# nRF52832_MCU.net
KiCad netlist of a schematic drawn in EAGLE
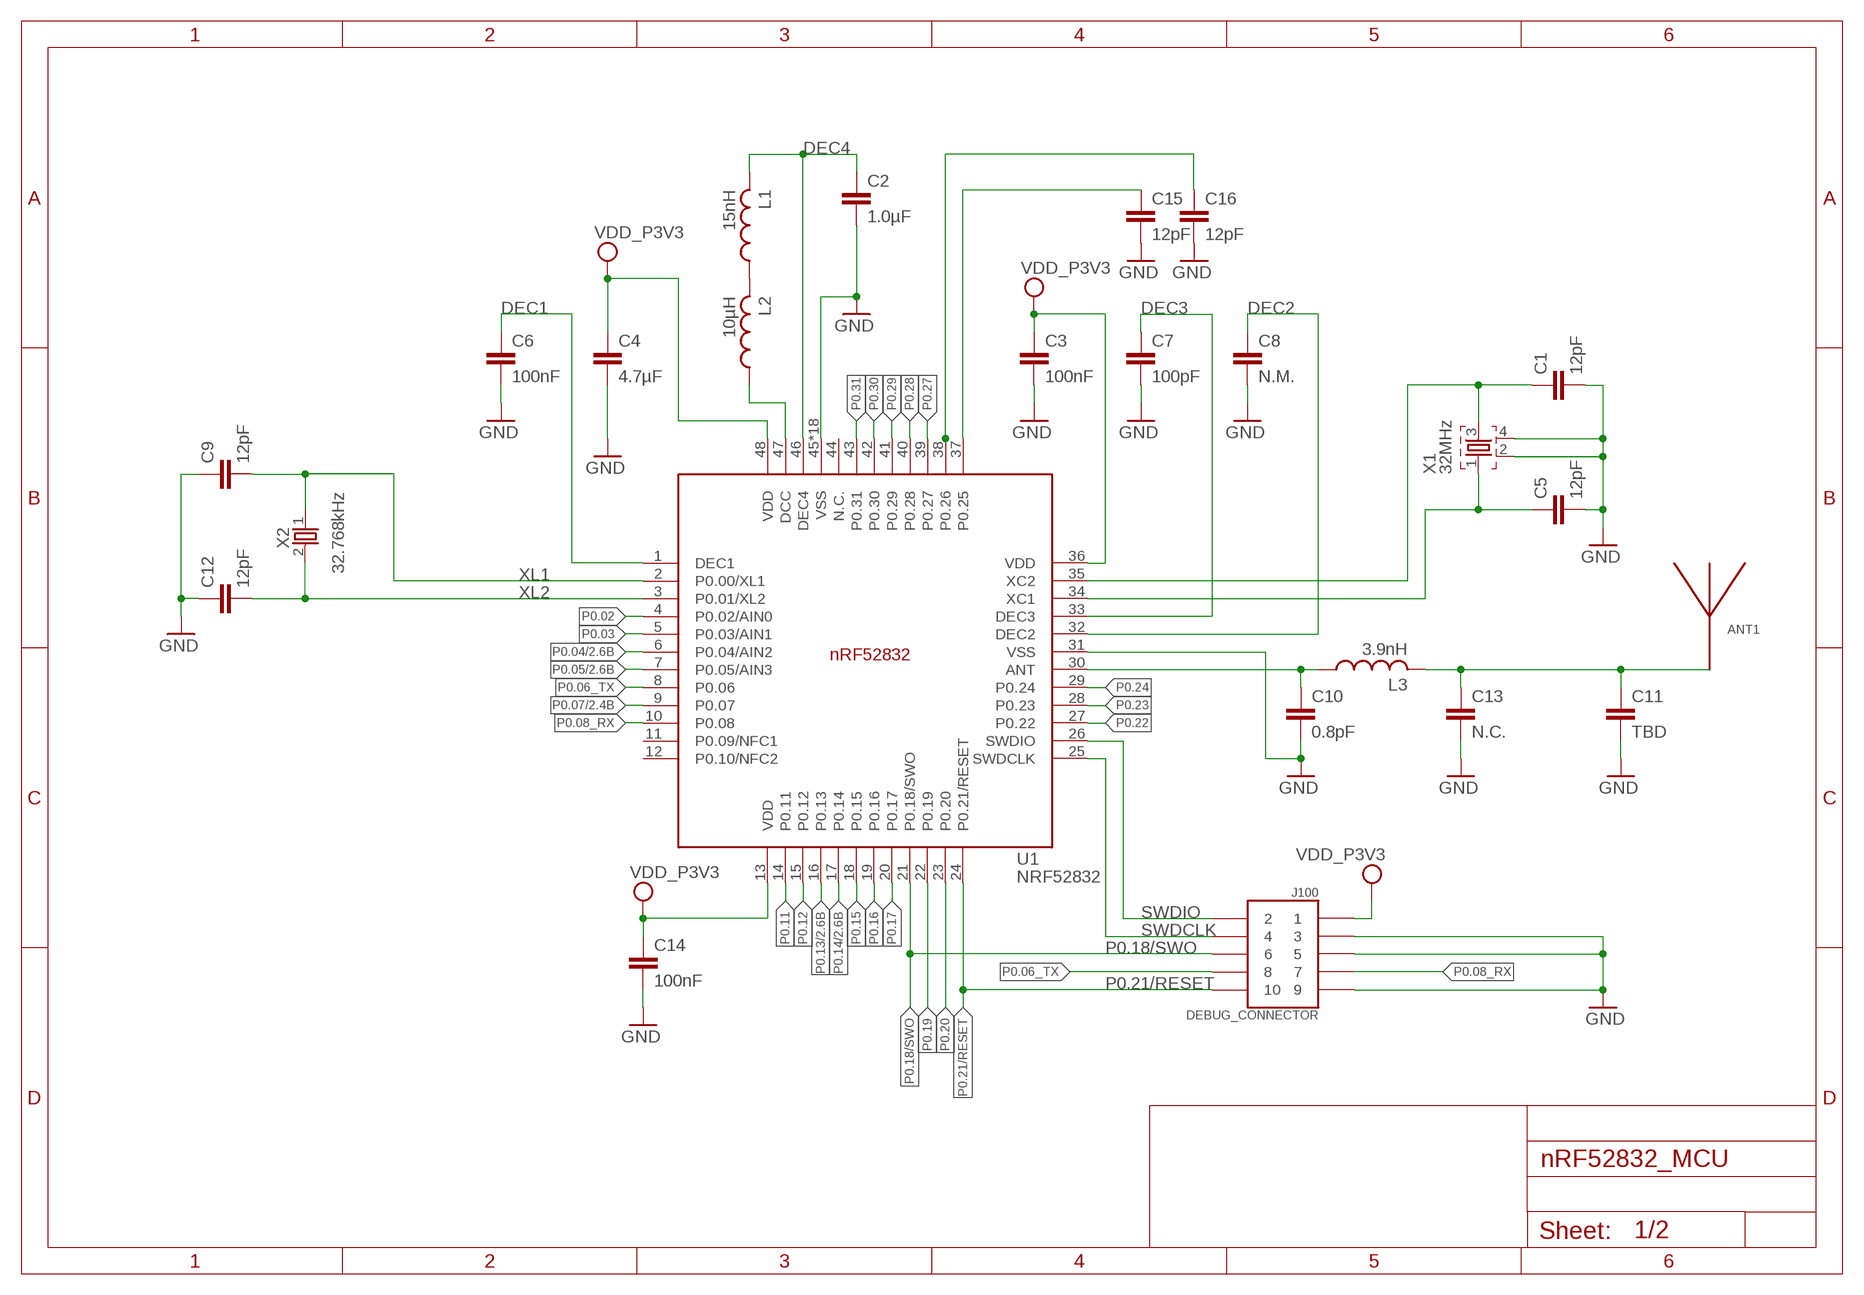
[diagram p0: schematic, sheet 1]
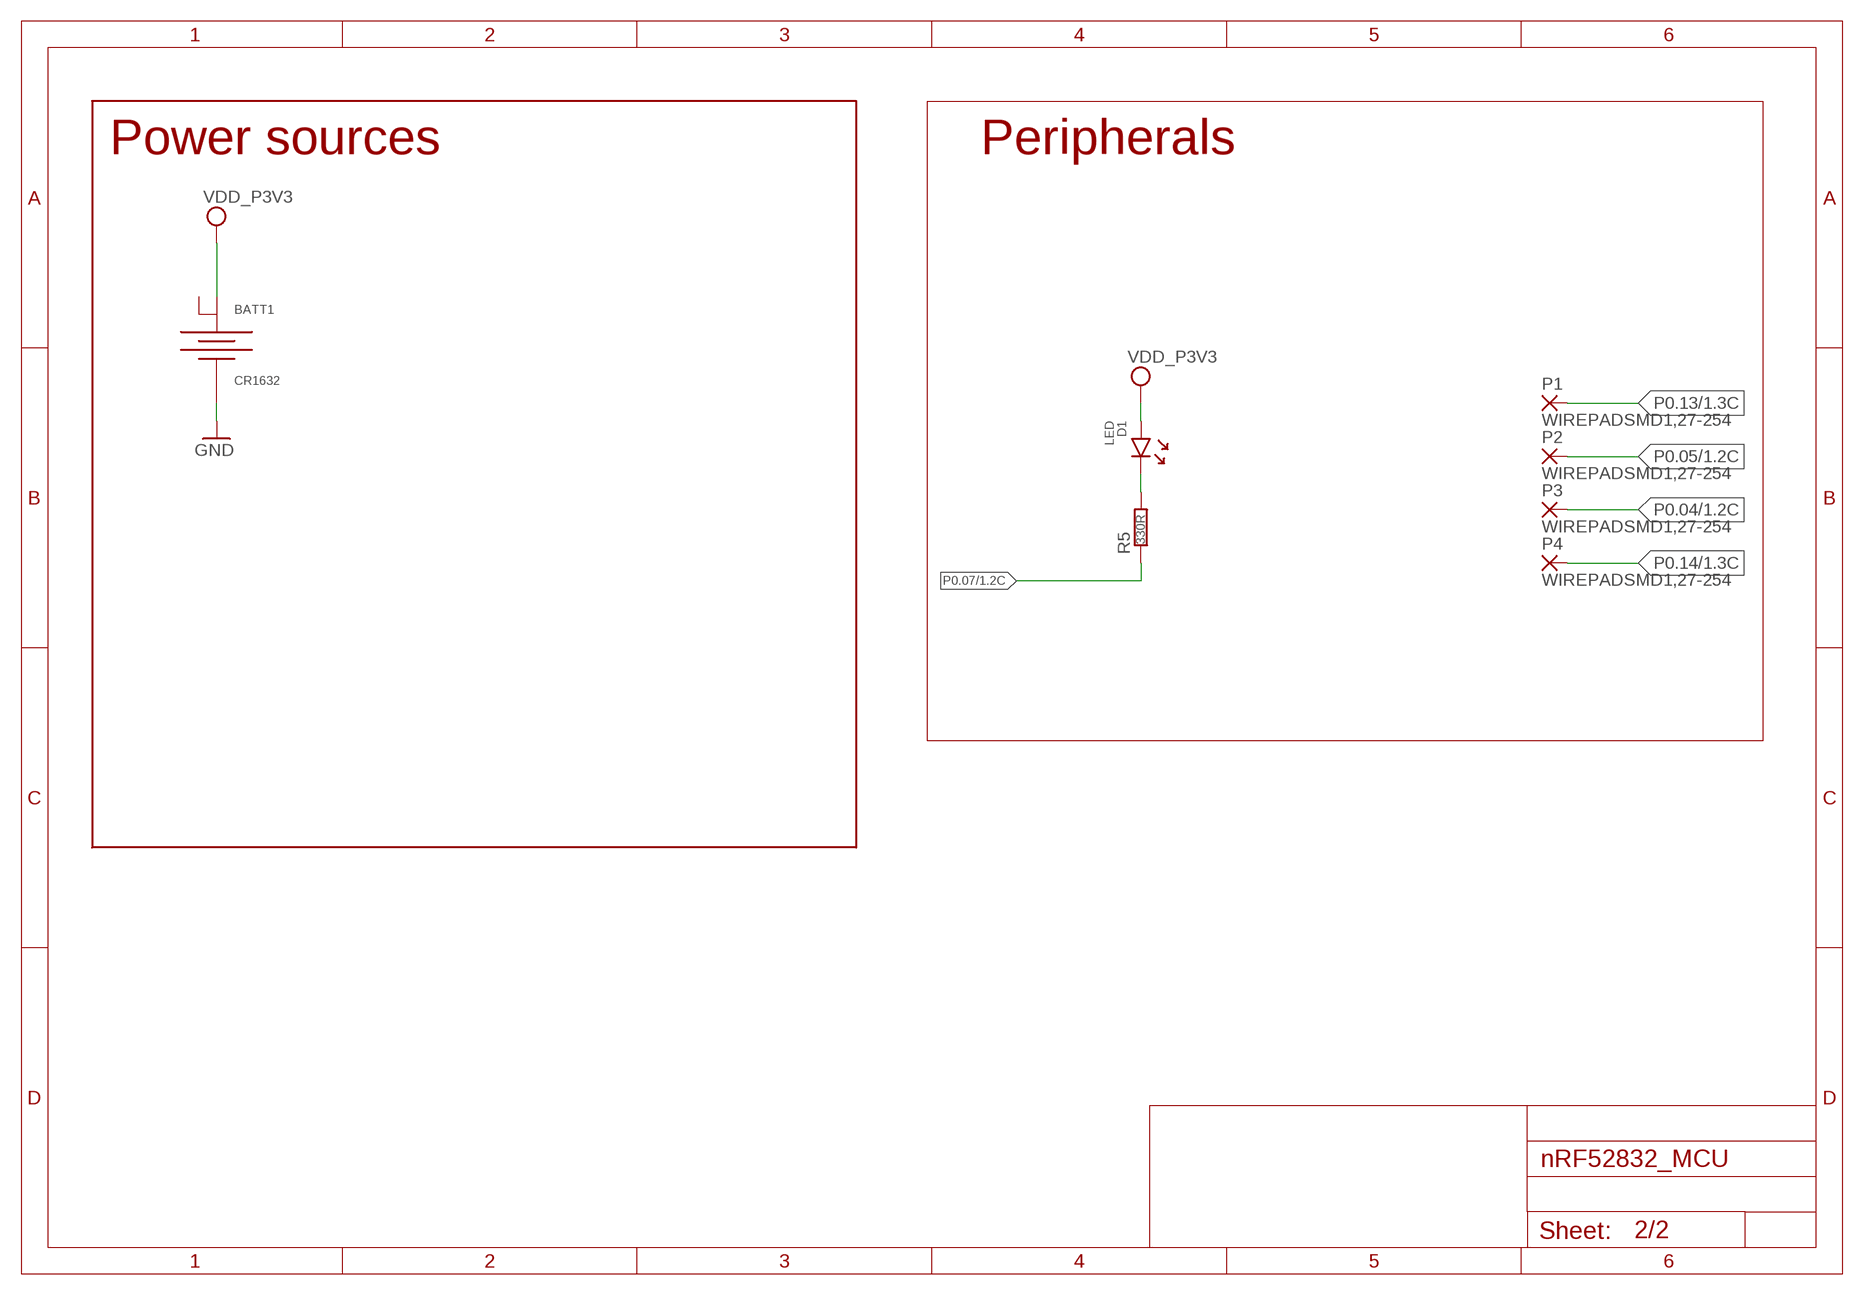
[diagram p1: schematic, sheet 2]

(export (version "E")
  (design (tool "Eeschema 10.0.6"))
  (components
    (comp (ref "BATT1")
      (value "CR1632")
      (footprint "eagle-import:CR1632_HOLDER_TH")
      (libsource (lib "eagle-import") (part "CR1632"))
    )
    (comp (ref "D1")
      (value "LED")
      (footprint "eagle-import:DIOC0603_N")
      (libsource (lib "eagle-import") (part "LED"))
    )
    (comp (ref "P1")
      (value "WIREPADSMD1,27-254")
      (footprint "eagle-import:SMD1,27-2,54")
      (libsource (lib "eagle-import") (part "WIREPADSMD1,27-254"))
    )
    (comp (ref "P2")
      (value "WIREPADSMD1,27-254")
      (footprint "eagle-import:SMD1,27-2,54")
      (libsource (lib "eagle-import") (part "WIREPADSMD1,27-254"))
    )
    (comp (ref "P3")
      (value "WIREPADSMD1,27-254")
      (footprint "eagle-import:SMD1,27-2,54")
      (libsource (lib "eagle-import") (part "WIREPADSMD1,27-254"))
    )
    (comp (ref "P4")
      (value "WIREPADSMD1,27-254")
      (footprint "eagle-import:SMD1,27-2,54")
      (libsource (lib "eagle-import") (part "WIREPADSMD1,27-254"))
    )
    (comp (ref "R5")
      (value "330R")
      (footprint "eagle-import:RESC0402_N")
      (libsource (lib "eagle-import") (part "RESISTOR_0402_N"))
    )
    (comp (ref "ANT1")
      (value "ANTENNA_QUARTER-WAVE_MONOPOLE_MEANDERED_LEFT")
      (footprint "eagle-import:QWMP_MEANDERED_LEFT_+6")
      (libsource (lib "eagle-import") (part "ANTENNA_QUARTER-WAVE_MONOPOLE_MEANDERED_LEFT"))
    )
    (comp (ref "C1")
      (value "12pF")
      (footprint "eagle-import:RESC0402_N")
      (libsource (lib "eagle-import") (part "CAPACITOR_0402_N"))
    )
    (comp (ref "C2")
      (value "1.0µF")
      (footprint "eagle-import:RESC0603_N")
      (libsource (lib "eagle-import") (part "CAPACITOR_0603_N"))
    )
    (comp (ref "C3")
      (value "100nF")
      (footprint "eagle-import:RESC0402_N")
      (libsource (lib "eagle-import") (part "CAPACITOR_0402_N"))
    )
    (comp (ref "C4")
      (value "4.7µF")
      (footprint "eagle-import:RESC0603_N")
      (libsource (lib "eagle-import") (part "CAPACITOR_0603_N"))
    )
    (comp (ref "C5")
      (value "12pF")
      (footprint "eagle-import:RESC0402_N")
      (libsource (lib "eagle-import") (part "CAPACITOR_0402_N"))
    )
    (comp (ref "C6")
      (value "100nF")
      (footprint "eagle-import:RESC0402_N")
      (libsource (lib "eagle-import") (part "CAPACITOR_0402_N"))
    )
    (comp (ref "C7")
      (value "100pF")
      (footprint "eagle-import:RESC0402_N")
      (libsource (lib "eagle-import") (part "CAPACITOR_0402_N"))
    )
    (comp (ref "C8")
      (value "N.M.")
      (footprint "eagle-import:RESC0402_N")
      (libsource (lib "eagle-import") (part "CAPACITOR_0402_N"))
    )
    (comp (ref "C9")
      (value "12pF")
      (footprint "eagle-import:RESC0402_N")
      (libsource (lib "eagle-import") (part "CAPACITOR_0402_N"))
    )
    (comp (ref "C10")
      (value "0.8pF")
      (footprint "eagle-import:RESC0402_N")
      (libsource (lib "eagle-import") (part "CAPACITOR_0402_N"))
    )
    (comp (ref "C11")
      (value "TBD")
      (footprint "eagle-import:RESC0402_N")
      (libsource (lib "eagle-import") (part "CAPACITOR_0402_N"))
    )
    (comp (ref "C12")
      (value "12pF")
      (footprint "eagle-import:RESC0402_N")
      (libsource (lib "eagle-import") (part "CAPACITOR_0402_N"))
    )
    (comp (ref "C13")
      (value "N.C.")
      (footprint "eagle-import:RESC0402_N")
      (libsource (lib "eagle-import") (part "CAPACITOR_0402_N"))
    )
    (comp (ref "C14")
      (value "100nF")
      (footprint "eagle-import:RESC0402_N")
      (libsource (lib "eagle-import") (part "CAPACITOR_0402_N"))
    )
    (comp (ref "C15")
      (value "12pF")
      (footprint "eagle-import:RESC0402_N")
      (libsource (lib "eagle-import") (part "CAPACITOR_0402_N"))
    )
    (comp (ref "C16")
      (value "12pF")
      (footprint "eagle-import:RESC0402_N")
      (libsource (lib "eagle-import") (part "CAPACITOR_0402_N"))
    )
    (comp (ref "J100")
      (value "DEBUG_CONNECTOR")
      (footprint "eagle-import:HDRV127P5X2-10_N")
      (libsource (lib "eagle-import") (part "DEBUG_CONNECTOR"))
    )
    (comp (ref "L1")
      (value "15nH")
      (footprint "eagle-import:RESC0402_N")
      (libsource (lib "eagle-import") (part "INDUCTOR_0402_N"))
    )
    (comp (ref "L2")
      (value "10µH")
      (footprint "eagle-import:RESC0603_N")
      (libsource (lib "eagle-import") (part "INDUCTOR_0603_N"))
    )
    (comp (ref "L3")
      (value "3.9nH")
      (footprint "eagle-import:RESC0402_N")
      (libsource (lib "eagle-import") (part "INDUCTOR_0402_N"))
    )
    (comp (ref "U1")
      (value "NRF52832")
      (footprint "eagle-import:QFN40P600X600X90-48_N")
      (libsource (lib "eagle-import") (part "NRF52832"))
    )
    (comp (ref "X1")
      (value "32MHz")
      (footprint "eagle-import:BT-XTAL_2016_N")
      (libsource (lib "eagle-import") (part "XTAL_32MHZ"))
    )
    (comp (ref "X2")
      (value "32.768kHz")
      (footprint "eagle-import:XTAL_3215_N")
      (libsource (lib "eagle-import") (part "XTAL_32KHZ"))
    )
  )
  (nets
    (net (code "1") (name "DEC1") (class "Default")
      (node (ref "C6") (pin "1") (pinfunction "1_1") (pintype "passive"))
      (node (ref "U1") (pin "1") (pinfunction "DEC1_1") (pintype "power_in"))
    )
    (net (code "2") (name "DEC2") (class "Default")
      (node (ref "C8") (pin "1") (pinfunction "1_1") (pintype "passive"))
      (node (ref "U1") (pin "32") (pinfunction "DEC2_32") (pintype "bidirectional"))
    )
    (net (code "3") (name "DEC3") (class "Default")
      (node (ref "C7") (pin "1") (pinfunction "1_1") (pintype "passive"))
      (node (ref "U1") (pin "33") (pinfunction "DEC3_33") (pintype "bidirectional"))
    )
    (net (code "4") (name "DEC4") (class "Default")
      (node (ref "C2") (pin "1") (pinfunction "1_1") (pintype "passive"))
      (node (ref "L1") (pin "2") (pinfunction "2_2") (pintype "passive"))
      (node (ref "U1") (pin "46") (pinfunction "DEC4_46") (pintype "power_in"))
    )
    (net (code "5") (name "GND") (class "Default")
      (node (ref "BATT1") (pin "1") (pinfunction "-_1") (pintype "bidirectional"))
      (node (ref "C1") (pin "2") (pinfunction "2_2") (pintype "passive"))
      (node (ref "C10") (pin "2") (pinfunction "2_2") (pintype "passive"))
      (node (ref "C11") (pin "2") (pinfunction "2_2") (pintype "passive"))
      (node (ref "C12") (pin "1") (pinfunction "1_1") (pintype "passive"))
      (node (ref "C13") (pin "2") (pinfunction "2_2") (pintype "passive"))
      (node (ref "C14") (pin "2") (pinfunction "2_2") (pintype "passive"))
      (node (ref "C15") (pin "2") (pinfunction "2_2") (pintype "passive"))
      (node (ref "C16") (pin "2") (pinfunction "2_2") (pintype "passive"))
      (node (ref "C2") (pin "2") (pinfunction "2_2") (pintype "passive"))
      (node (ref "C3") (pin "2") (pinfunction "2_2") (pintype "passive"))
      (node (ref "C4") (pin "2") (pinfunction "2_2") (pintype "passive"))
      (node (ref "C5") (pin "2") (pinfunction "2_2") (pintype "passive"))
      (node (ref "C6") (pin "2") (pinfunction "2_2") (pintype "passive"))
      (node (ref "C7") (pin "2") (pinfunction "2_2") (pintype "passive"))
      (node (ref "C8") (pin "2") (pinfunction "2_2") (pintype "passive"))
      (node (ref "C9") (pin "1") (pinfunction "1_1") (pintype "passive"))
      (node (ref "J100") (pin "3") (pinfunction "3_3") (pintype "bidirectional"))
      (node (ref "J100") (pin "5") (pinfunction "5_5") (pintype "bidirectional"))
      (node (ref "J100") (pin "9") (pinfunction "9_9") (pintype "bidirectional"))
      (node (ref "U1") (pin "31") (pinfunction "VSS_31") (pintype "bidirectional"))
      (node (ref "U1") (pin "45") (pinfunction "VSS_45") (pintype "power_in"))
      (node (ref "U1") (pin "PAD") (pinfunction "VSS_PAD") (pintype "power_in"))
      (node (ref "U1") (pin "PAD@VIA01") (pinfunction "VSS_PAD@VIA01") (pintype "power_in"))
      (node (ref "U1") (pin "PAD@VIA02") (pinfunction "VSS_PAD@VIA02") (pintype "power_in"))
      (node (ref "U1") (pin "PAD@VIA03") (pinfunction "VSS_PAD@VIA03") (pintype "power_in"))
      (node (ref "U1") (pin "PAD@VIA04") (pinfunction "VSS_PAD@VIA04") (pintype "power_in"))
      (node (ref "U1") (pin "PAD@VIA05") (pinfunction "VSS_PAD@VIA05") (pintype "power_in"))
      (node (ref "U1") (pin "PAD@VIA06") (pinfunction "VSS_PAD@VIA06") (pintype "power_in"))
      (node (ref "U1") (pin "PAD@VIA07") (pinfunction "VSS_PAD@VIA07") (pintype "power_in"))
      (node (ref "U1") (pin "PAD@VIA08") (pinfunction "VSS_PAD@VIA08") (pintype "power_in"))
      (node (ref "U1") (pin "PAD@VIA09") (pinfunction "VSS_PAD@VIA09") (pintype "power_in"))
      (node (ref "U1") (pin "PAD@VIA10") (pinfunction "VSS_PAD@VIA10") (pintype "power_in"))
      (node (ref "U1") (pin "PAD@VIA11") (pinfunction "VSS_PAD@VIA11") (pintype "power_in"))
      (node (ref "U1") (pin "PAD@VIA12") (pinfunction "VSS_PAD@VIA12") (pintype "power_in"))
      (node (ref "U1") (pin "PAD@VIA13") (pinfunction "VSS_PAD@VIA13") (pintype "power_in"))
      (node (ref "U1") (pin "PAD@VIA14") (pinfunction "VSS_PAD@VIA14") (pintype "power_in"))
      (node (ref "U1") (pin "PAD@VIA15") (pinfunction "VSS_PAD@VIA15") (pintype "power_in"))
      (node (ref "U1") (pin "PAD@VIA16") (pinfunction "VSS_PAD@VIA16") (pintype "power_in"))
      (node (ref "X1") (pin "2") (pinfunction "2_2") (pintype "passive"))
      (node (ref "X1") (pin "4") (pinfunction "4_4") (pintype "passive"))
    )
    (net (code "6") (name "Net-(ANT1-PadP$1)") (class "Default")
      (node (ref "ANT1") (pin "P$1") (pinfunction "P$1_P$1") (pintype "bidirectional"))
      (node (ref "C11") (pin "1") (pinfunction "1_1") (pintype "passive"))
      (node (ref "C13") (pin "1") (pinfunction "1_1") (pintype "passive"))
      (node (ref "L3") (pin "2") (pinfunction "2_2") (pintype "passive"))
    )
    (net (code "7") (name "Net-(D1-C)") (class "Default")
      (node (ref "D1") (pin "1") (pinfunction "C_1") (pintype "bidirectional"))
      (node (ref "R5") (pin "2") (pinfunction "2_2") (pintype "passive"))
    )
    (net (code "8") (name "Net-(L1-Pad1)") (class "Default")
      (node (ref "L1") (pin "1") (pinfunction "1_1") (pintype "passive"))
      (node (ref "L2") (pin "2") (pinfunction "2_2") (pintype "passive"))
    )
    (net (code "9") (name "Net-(U1-ANT)") (class "Default")
      (node (ref "C10") (pin "1") (pinfunction "1_1") (pintype "passive"))
      (node (ref "L3") (pin "1") (pinfunction "1_1") (pintype "passive"))
      (node (ref "U1") (pin "30") (pinfunction "ANT_30") (pintype "bidirectional"))
    )
    (net (code "10") (name "Net-(U1-DCC)") (class "Default")
      (node (ref "L2") (pin "1") (pinfunction "1_1") (pintype "passive"))
      (node (ref "U1") (pin "47") (pinfunction "DCC_47") (pintype "output"))
    )
    (net (code "11") (name "Net-(U1-P0.25)") (class "Default")
      (node (ref "C15") (pin "1") (pinfunction "1_1") (pintype "passive"))
      (node (ref "U1") (pin "37") (pinfunction "P0.25_37") (pintype "bidirectional"))
    )
    (net (code "12") (name "Net-(U1-P0.26)") (class "Default")
      (node (ref "C16") (pin "1") (pinfunction "1_1") (pintype "passive"))
      (node (ref "U1") (pin "38") (pinfunction "P0.26_38") (pintype "bidirectional"))
    )
    (net (code "13") (name "Net-(U1-XC1)") (class "Default")
      (node (ref "C5") (pin "1") (pinfunction "1_1") (pintype "passive"))
      (node (ref "U1") (pin "34") (pinfunction "XC1_34") (pintype "input"))
      (node (ref "X1") (pin "1") (pinfunction "1_1") (pintype "passive"))
    )
    (net (code "14") (name "Net-(U1-XC2)") (class "Default")
      (node (ref "C1") (pin "1") (pinfunction "1_1") (pintype "passive"))
      (node (ref "U1") (pin "35") (pinfunction "XC2_35") (pintype "output"))
      (node (ref "X1") (pin "3") (pinfunction "3_3") (pintype "passive"))
    )
    (net (code "15") (name "P0.02") (class "Default")
      (node (ref "U1") (pin "4") (pinfunction "P0.02/AIN0_4") (pintype "bidirectional"))
    )
    (net (code "16") (name "P0.03") (class "Default")
      (node (ref "U1") (pin "5") (pinfunction "P0.03/AIN1_5") (pintype "bidirectional"))
    )
    (net (code "17") (name "P0.04") (class "Default")
      (node (ref "P3") (pin "1") (pinfunction "P_1") (pintype "passive"))
      (node (ref "U1") (pin "6") (pinfunction "P0.04/AIN2_6") (pintype "bidirectional"))
    )
    (net (code "18") (name "P0.05") (class "Default")
      (node (ref "P2") (pin "1") (pinfunction "P_1") (pintype "passive"))
      (node (ref "U1") (pin "7") (pinfunction "P0.05/AIN3_7") (pintype "bidirectional"))
    )
    (net (code "19") (name "P0.06_TX") (class "Default")
      (node (ref "J100") (pin "8") (pinfunction "8_8") (pintype "bidirectional"))
      (node (ref "U1") (pin "8") (pinfunction "P0.06_8") (pintype "bidirectional"))
    )
    (net (code "20") (name "P0.07") (class "Default")
      (node (ref "R5") (pin "1") (pinfunction "1_1") (pintype "passive"))
      (node (ref "U1") (pin "9") (pinfunction "P0.07_9") (pintype "bidirectional"))
    )
    (net (code "21") (name "P0.08_RX") (class "Default")
      (node (ref "J100") (pin "7") (pinfunction "7_7") (pintype "bidirectional"))
      (node (ref "U1") (pin "10") (pinfunction "P0.08_10") (pintype "bidirectional"))
    )
    (net (code "22") (name "P0.11") (class "Default")
      (node (ref "U1") (pin "14") (pinfunction "P0.11_14") (pintype "bidirectional"))
    )
    (net (code "23") (name "P0.12") (class "Default")
      (node (ref "U1") (pin "15") (pinfunction "P0.12_15") (pintype "bidirectional"))
    )
    (net (code "24") (name "P0.13") (class "Default")
      (node (ref "P1") (pin "1") (pinfunction "P_1") (pintype "passive"))
      (node (ref "U1") (pin "16") (pinfunction "P0.13_16") (pintype "bidirectional"))
    )
    (net (code "25") (name "P0.14") (class "Default")
      (node (ref "P4") (pin "1") (pinfunction "P_1") (pintype "passive"))
      (node (ref "U1") (pin "17") (pinfunction "P0.14_17") (pintype "bidirectional"))
    )
    (net (code "26") (name "P0.15") (class "Default")
      (node (ref "U1") (pin "18") (pinfunction "P0.15_18") (pintype "bidirectional"))
    )
    (net (code "27") (name "P0.16") (class "Default")
      (node (ref "U1") (pin "19") (pinfunction "P0.16_19") (pintype "bidirectional"))
    )
    (net (code "28") (name "P0.17") (class "Default")
      (node (ref "U1") (pin "20") (pinfunction "P0.17_20") (pintype "bidirectional"))
    )
    (net (code "29") (name "P0.18{slash}SWO") (class "Default")
      (node (ref "J100") (pin "6") (pinfunction "6_6") (pintype "bidirectional"))
      (node (ref "U1") (pin "21") (pinfunction "P0.18/SWO_21") (pintype "bidirectional"))
    )
    (net (code "30") (name "P0.19") (class "Default")
      (node (ref "U1") (pin "22") (pinfunction "P0.19_22") (pintype "bidirectional"))
    )
    (net (code "31") (name "P0.20") (class "Default")
      (node (ref "U1") (pin "23") (pinfunction "P0.20_23") (pintype "bidirectional"))
    )
    (net (code "32") (name "P0.21{slash}RESET") (class "Default")
      (node (ref "J100") (pin "10") (pinfunction "10_10") (pintype "bidirectional"))
      (node (ref "U1") (pin "24") (pinfunction "P0.21/RESET_24") (pintype "bidirectional"))
    )
    (net (code "33") (name "P0.22") (class "Default")
      (node (ref "U1") (pin "27") (pinfunction "P0.22_27") (pintype "bidirectional"))
    )
    (net (code "34") (name "P0.23") (class "Default")
      (node (ref "U1") (pin "28") (pinfunction "P0.23_28") (pintype "bidirectional"))
    )
    (net (code "35") (name "P0.24") (class "Default")
      (node (ref "U1") (pin "29") (pinfunction "P0.24_29") (pintype "bidirectional"))
    )
    (net (code "36") (name "P0.27") (class "Default")
      (node (ref "U1") (pin "39") (pinfunction "P0.27_39") (pintype "bidirectional"))
    )
    (net (code "37") (name "P0.28") (class "Default")
      (node (ref "U1") (pin "40") (pinfunction "P0.28_40") (pintype "bidirectional"))
    )
    (net (code "38") (name "P0.29") (class "Default")
      (node (ref "U1") (pin "41") (pinfunction "P0.29_41") (pintype "bidirectional"))
    )
    (net (code "39") (name "P0.30") (class "Default")
      (node (ref "U1") (pin "42") (pinfunction "P0.30_42") (pintype "bidirectional"))
    )
    (net (code "40") (name "P0.31") (class "Default")
      (node (ref "U1") (pin "43") (pinfunction "P0.31_43") (pintype "bidirectional"))
    )
    (net (code "41") (name "SWDCLK") (class "Default")
      (node (ref "J100") (pin "4") (pinfunction "4_4") (pintype "bidirectional"))
      (node (ref "U1") (pin "25") (pinfunction "SWDCLK_25") (pintype "input"))
    )
    (net (code "42") (name "SWDIO") (class "Default")
      (node (ref "J100") (pin "2") (pinfunction "2_2") (pintype "bidirectional"))
      (node (ref "U1") (pin "26") (pinfunction "SWDIO_26") (pintype "bidirectional"))
    )
    (net (code "43") (name "VDD_P3V3") (class "Default")
      (node (ref "BATT1") (pin "2") (pinfunction "+_2") (pintype "bidirectional"))
      (node (ref "C14") (pin "1") (pinfunction "1_1") (pintype "passive"))
      (node (ref "C3") (pin "1") (pinfunction "1_1") (pintype "passive"))
      (node (ref "C4") (pin "1") (pinfunction "1_1") (pintype "passive"))
      (node (ref "D1") (pin "2") (pinfunction "A_2") (pintype "bidirectional"))
      (node (ref "J100") (pin "1") (pinfunction "1_1") (pintype "bidirectional"))
      (node (ref "U1") (pin "13") (pinfunction "VDD_13") (pintype "power_in"))
      (node (ref "U1") (pin "36") (pinfunction "VDD_36") (pintype "power_in"))
      (node (ref "U1") (pin "48") (pinfunction "VDD_48") (pintype "power_in"))
    )
    (net (code "44") (name "XL1") (class "Default")
      (node (ref "C9") (pin "2") (pinfunction "2_2") (pintype "passive"))
      (node (ref "U1") (pin "2") (pinfunction "P0.00/XL1_2") (pintype "bidirectional"))
      (node (ref "X2") (pin "1") (pinfunction "1_1") (pintype "passive"))
    )
    (net (code "45") (name "XL2") (class "Default")
      (node (ref "C12") (pin "2") (pinfunction "2_2") (pintype "passive"))
      (node (ref "U1") (pin "3") (pinfunction "P0.01/XL2_3") (pintype "bidirectional"))
      (node (ref "X2") (pin "2") (pinfunction "2_2") (pintype "passive"))
    )
    (net (code "46") (name "unconnected-(BATT1-+2-Pad3)") (class "Default")
      (node (ref "BATT1") (pin "3") (pinfunction "+2_3") (pintype "bidirectional"))
    )
    (net (code "47") (name "unconnected-(U1-N.C.-Pad44)") (class "Default")
      (node (ref "U1") (pin "44") (pinfunction "N.C._44") (pintype "no_connect"))
    )
    (net (code "48") (name "unconnected-(U1-P0.09{slash}NFC1-Pad11)") (class "Default")
      (node (ref "U1") (pin "11") (pinfunction "P0.09/NFC1_11") (pintype "bidirectional"))
    )
    (net (code "49") (name "unconnected-(U1-P0.10{slash}NFC2-Pad12)") (class "Default")
      (node (ref "U1") (pin "12") (pinfunction "P0.10/NFC2_12") (pintype "bidirectional"))
    )
  )
)
